# PCB_1b.net
KiCad netlist of a schematic drawn in EAGLE
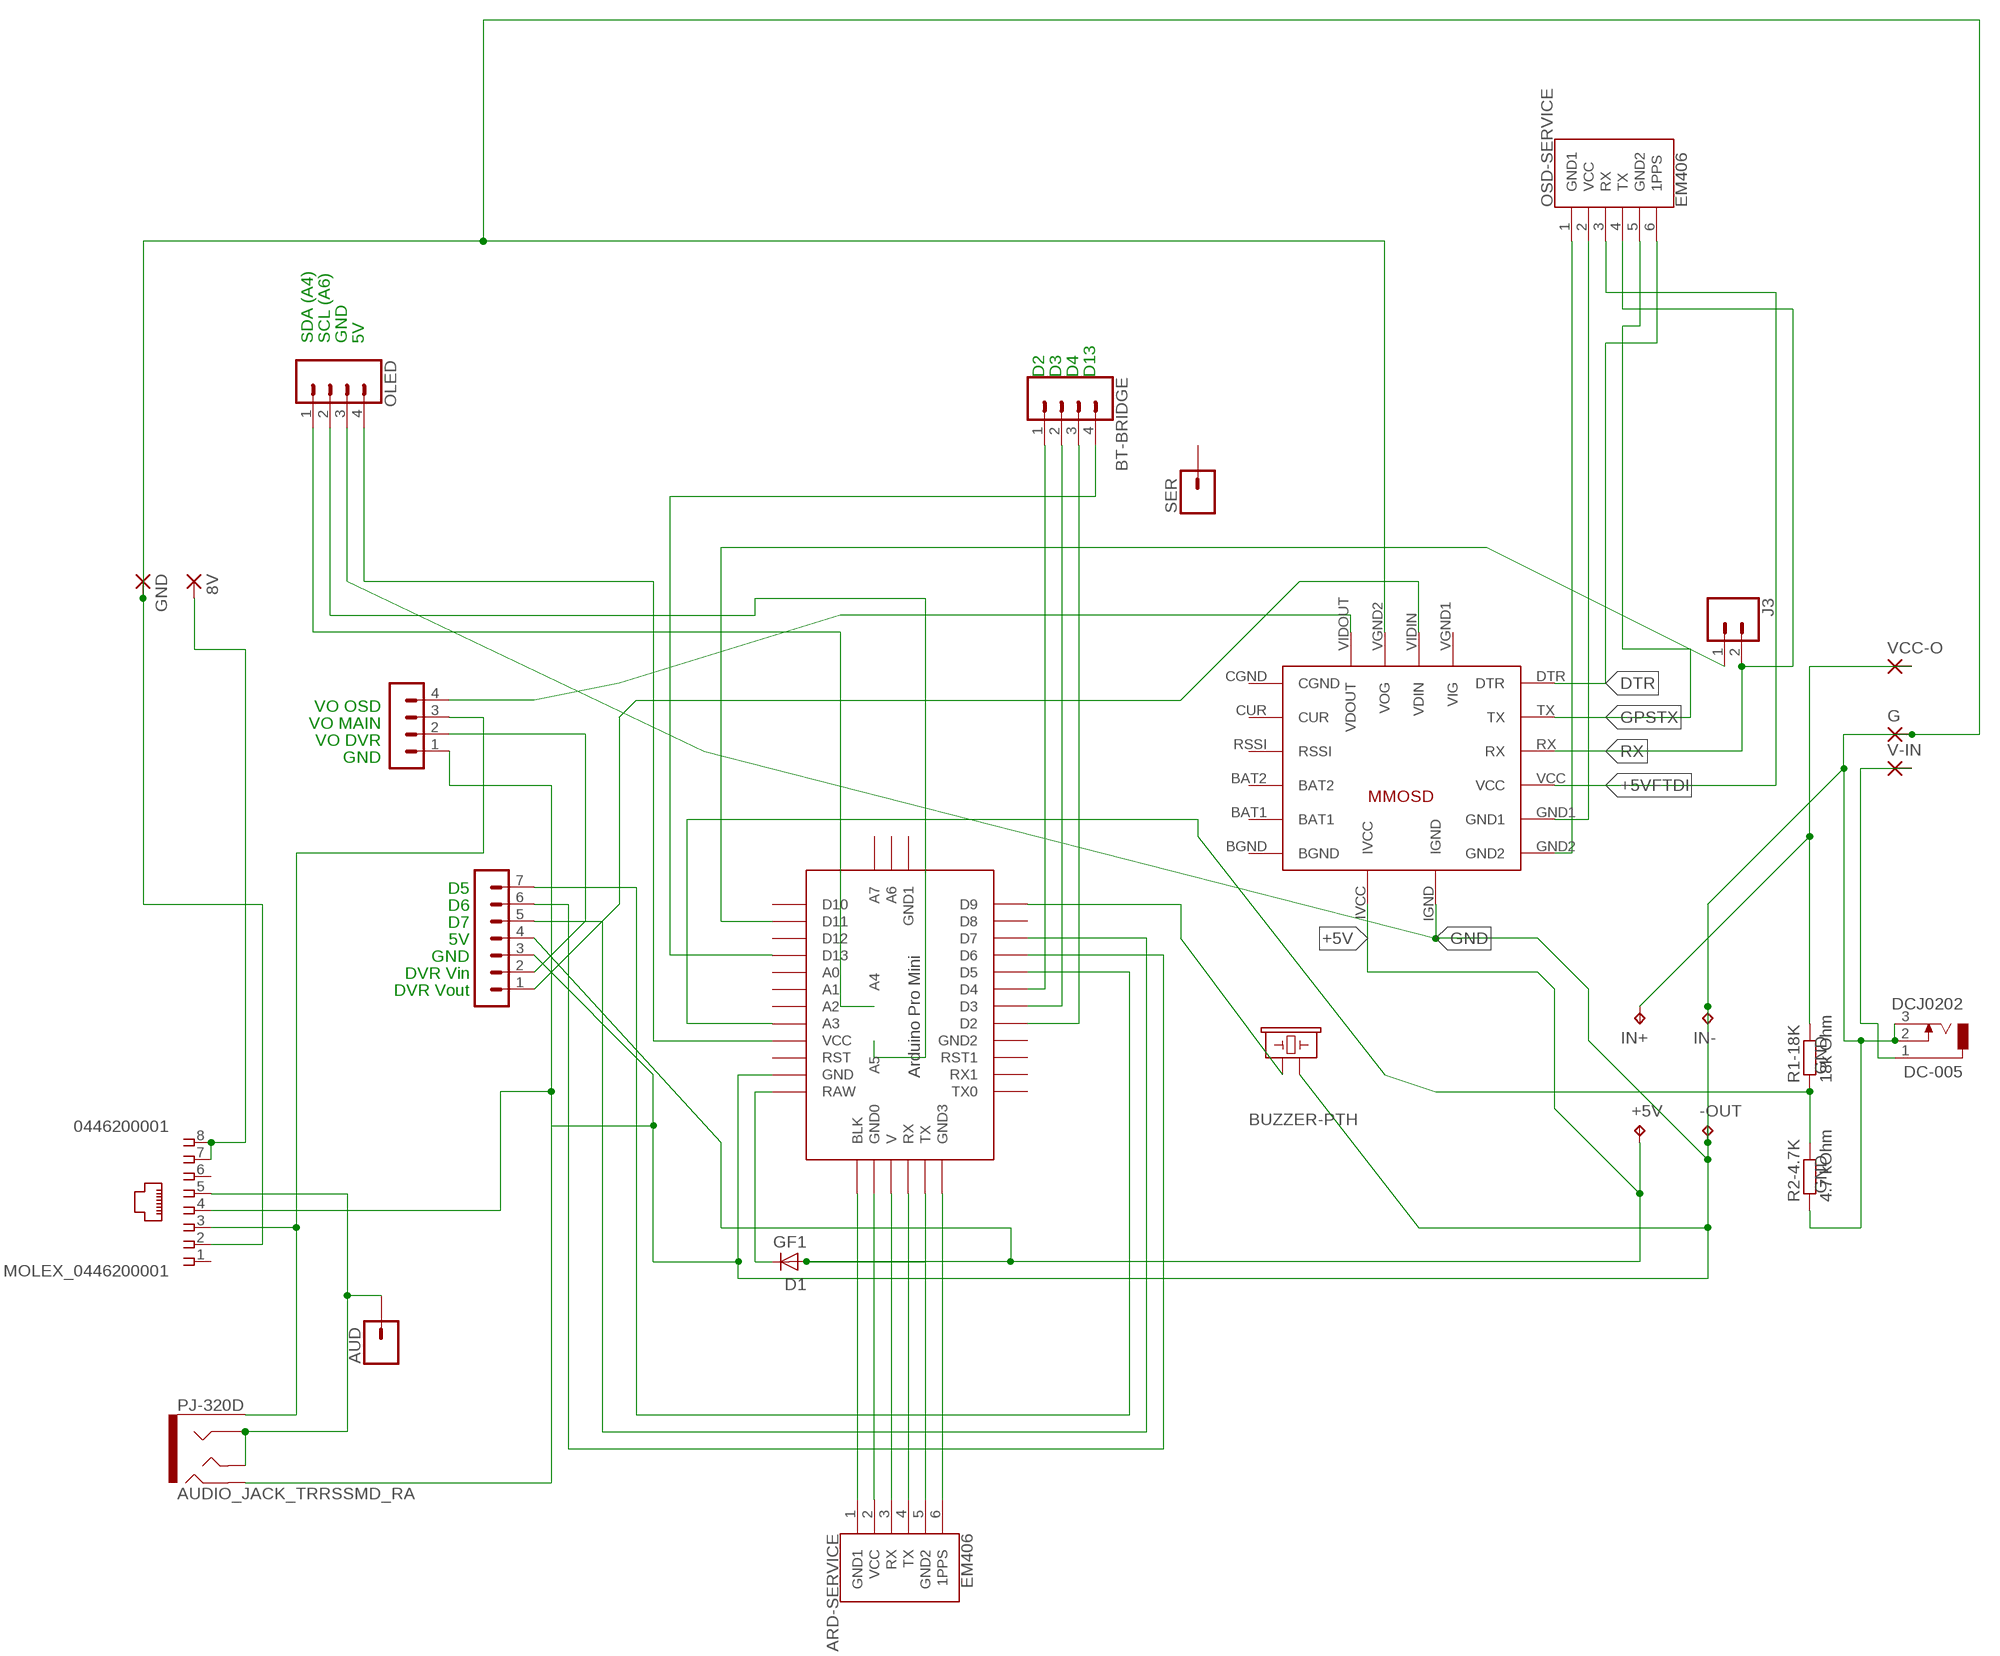
[diagram p0: schematic, sheet 1]

(export (version "E")
  (design (tool "Eeschema 10.0.6"))
  (components
    (comp (ref "+5V")
      (value "TPTP20SQ")
      (footprint "eagle-import:TP20SQ")
      (libsource (lib "eagle-import") (part "TPTP20SQ"))
    )
    (comp (ref "-OUT")
      (value "TPTP20SQ")
      (footprint "eagle-import:TP20SQ")
      (libsource (lib "eagle-import") (part "TPTP20SQ"))
    )
    (comp (ref "8V")
      (value "2,54/1,1")
      (footprint "eagle-import:2,54_1,1")
      (libsource (lib "eagle-import") (part "2,54/1,1"))
    )
    (comp (ref "ARD-SERVICE")
      (value "EM406")
      (footprint "eagle-import:1X06-1MM")
      (libsource (lib "eagle-import") (part "EM406"))
    )
    (comp (ref "AUD")
      (value "CONN_01")
      (footprint "eagle-import:1X01")
      (libsource (lib "eagle-import") (part "CONN_01"))
    )
    (comp (ref "BT-BRIDGE")
      (value "CONN_04")
      (footprint "eagle-import:1X04")
      (libsource (lib "eagle-import") (part "CONN_04"))
    )
    (comp (ref "BUZZ")
      (value "BUZZER-PTH")
      (footprint "eagle-import:BUZZER-12MM")
      (fields (field (name "SPICEPREFIX") "X"))
      (libsource (lib "eagle-import") (part "BUZZER-PTH"))
    )
    (comp (ref "D1")
      (value "GF1")
      (footprint "eagle-import:SMA-DO214AC")
      (libsource (lib "eagle-import") (part "GF1"))
    )
    (comp (ref "DC-005")
      (value "DCJ0202")
      (footprint "eagle-import:DCJ0202")
      (libsource (lib "eagle-import") (part "DCJ0202"))
    )
    (comp (ref "DVR/MODULE-IO")
      (value "MA07-1")
      (footprint "eagle-import:MA07-1")
      (libsource (lib "eagle-import") (part "MA07-1"))
    )
    (comp (ref "G")
      (value "2,54/1,1")
      (footprint "eagle-import:2,54_1,1")
      (libsource (lib "eagle-import") (part "2,54/1,1"))
    )
    (comp (ref "GND")
      (value "2,54/1,1")
      (footprint "eagle-import:2,54_1,1")
      (libsource (lib "eagle-import") (part "2,54/1,1"))
    )
    (comp (ref "IN+")
      (value "TPTP20SQ")
      (footprint "eagle-import:TP20SQ")
      (libsource (lib "eagle-import") (part "TPTP20SQ"))
    )
    (comp (ref "IN-")
      (value "TPTP20SQ")
      (footprint "eagle-import:TP20SQ")
      (libsource (lib "eagle-import") (part "TPTP20SQ"))
    )
    (comp (ref "J3")
      (value "CONN_02")
      (footprint "eagle-import:1X02")
      (libsource (lib "eagle-import") (part "CONN_02"))
    )
    (comp (ref "MINIMOSD")
      (value "MICROMINIMOSDPWR")
      (footprint "eagle-import:MMOSDNVDVID")
      (libsource (lib "eagle-import") (part "MICROMINIMOSDPWR"))
    )
    (comp (ref "MOLEX_0446200001")
      (value "0446200001")
      (footprint "eagle-import:0446200001")
      (fields (field (name "MF") "MOLEX"))
      (libsource (lib "eagle-import") (part "0446200001"))
    )
    (comp (ref "OLED")
      (value "CONN_04")
      (footprint "eagle-import:1X04")
      (libsource (lib "eagle-import") (part "CONN_04"))
    )
    (comp (ref "OSD-SERVICE")
      (value "EM406")
      (footprint "eagle-import:1X06-1MM")
      (libsource (lib "eagle-import") (part "EM406"))
    )
    (comp (ref "PJ-320D")
      (value "AUDIO_JACK_TRRSSMD_RA")
      (footprint "eagle-import:AUDIO_JACK_3.5MM_TRRS_SMD_RA")
      (libsource (lib "eagle-import") (part "AUDIO_JACK_TRRSSMD_RA"))
    )
    (comp (ref "R1-18K")
      (value "18k Ohm")
      (footprint "eagle-import:M1206")
      (libsource (lib "eagle-import") (part "R-EU_M1206"))
    )
    (comp (ref "R2-4.7K")
      (value "4.7 kOhm")
      (footprint "eagle-import:M1206")
      (libsource (lib "eagle-import") (part "R-EU_M1206"))
    )
    (comp (ref "SER")
      (value "CONN_01")
      (footprint "eagle-import:1X01")
      (libsource (lib "eagle-import") (part "CONN_01"))
    )
    (comp (ref "U$1")
      (value "ABK-PRO-MINI")
      (footprint "eagle-import:ABK-PRO-MINI")
      (libsource (lib "eagle-import") (part "ABK-PRO-MINI"))
    )
    (comp (ref "V-IN")
      (value "2,54/1,1")
      (footprint "eagle-import:2,54_1,1")
      (libsource (lib "eagle-import") (part "2,54/1,1"))
    )
    (comp (ref "V-IO")
      (value "MA04-1")
      (footprint "eagle-import:MA04-1")
      (libsource (lib "eagle-import") (part "MA04-1"))
    )
    (comp (ref "VCC-O")
      (value "2,54/1,1")
      (footprint "eagle-import:2,54_1,1")
      (libsource (lib "eagle-import") (part "2,54/1,1"))
    )
  )
  (nets
    (net (code "1") (name "+5V") (class "Default")
      (node (ref "+5V") (pin "TP") (pinfunction "TP_TP") (pintype "input"))
      (node (ref "D1") (pin "A") (pinfunction "A_A") (pintype "passive"))
      (node (ref "DVR/MODULE-IO") (pin "4") (pinfunction "4_4") (pintype "passive"))
      (node (ref "MINIMOSD") (pin "IVCC") (pinfunction "IVCC_IVCC") (pintype "power_in"))
    )
    (net (code "2") (name "+5VFTDI") (class "Default")
      (node (ref "MINIMOSD") (pin "VCC") (pinfunction "VCC_VCC") (pintype "power_in"))
      (node (ref "OSD-SERVICE") (pin "3") (pinfunction "RX_3") (pintype "bidirectional"))
    )
    (net (code "3") (name "/BAT1") (class "Default")
      (node (ref "MINIMOSD") (pin "BAT1") (pinfunction "BAT1_BAT1") (pintype "power_in"))
    )
    (net (code "4") (name "/BAT2") (class "Default")
      (node (ref "MINIMOSD") (pin "BAT2") (pinfunction "BAT2_BAT2") (pintype "power_in"))
    )
    (net (code "5") (name "/BGND") (class "Default")
      (node (ref "MINIMOSD") (pin "BGND") (pinfunction "BGND_BGND") (pintype "power_in"))
    )
    (net (code "6") (name "/CGND") (class "Default")
      (node (ref "MINIMOSD") (pin "CGND") (pinfunction "CGND_CGND") (pintype "power_in"))
    )
    (net (code "7") (name "DTR") (class "Default")
      (node (ref "MINIMOSD") (pin "DTR") (pinfunction "DTR_DTR") (pintype "bidirectional"))
      (node (ref "OSD-SERVICE") (pin "6") (pinfunction "1PPS_6") (pintype "bidirectional"))
    )
    (net (code "8") (name "GND") (class "Default")
      (node (ref "-OUT") (pin "TP") (pinfunction "TP_TP") (pintype "input"))
      (node (ref "BUZZ") (pin "-") (pinfunction "2_-") (pintype "passive"))
      (node (ref "DC-005") (pin "2") (pinfunction "2_2") (pintype "passive"))
      (node (ref "DC-005") (pin "3") (pinfunction "3_3") (pintype "passive"))
      (node (ref "DVR/MODULE-IO") (pin "3") (pinfunction "3_3") (pintype "passive"))
      (node (ref "G") (pin "1") (pinfunction "P_1") (pintype "passive"))
      (node (ref "GND") (pin "1") (pinfunction "P_1") (pintype "passive"))
      (node (ref "IN-") (pin "TP") (pinfunction "TP_TP") (pintype "input"))
      (node (ref "MINIMOSD") (pin "IGND") (pinfunction "IGND_IGND") (pintype "power_in"))
      (node (ref "MINIMOSD") (pin "VGND2") (pinfunction "VOG_VGND2") (pintype "output"))
      (node (ref "MOLEX_0446200001") (pin "2") (pinfunction "2_2") (pintype "passive"))
      (node (ref "MOLEX_0446200001") (pin "4") (pinfunction "4_4") (pintype "passive"))
      (node (ref "OLED") (pin "3") (pinfunction "3_3") (pintype "passive"))
      (node (ref "PJ-320D") (pin "RING2") (pinfunction "RING2_RING2") (pintype "bidirectional"))
      (node (ref "R2-4.7K") (pin "1") (pinfunction "1_1") (pintype "passive"))
      (node (ref "U$1") (pin "GND") (pinfunction "GND_GND") (pintype "bidirectional"))
      (node (ref "V-IO") (pin "1") (pinfunction "1_1") (pintype "passive"))
    )
    (net (code "9") (name "GPSTX") (class "Default")
      (node (ref "MINIMOSD") (pin "TX") (pinfunction "TX_TX") (pintype "output"))
      (node (ref "OSD-SERVICE") (pin "5") (pinfunction "GND2_5") (pintype "bidirectional"))
    )
    (net (code "10") (name "Net-(8V-P)") (class "Default")
      (node (ref "8V") (pin "1") (pinfunction "P_1") (pintype "passive"))
      (node (ref "MOLEX_0446200001") (pin "7") (pinfunction "7_7") (pintype "passive"))
      (node (ref "MOLEX_0446200001") (pin "8") (pinfunction "8_8") (pintype "passive"))
    )
    (net (code "11") (name "Net-(ARD-SERVICE-1PPS)") (class "Default")
      (node (ref "ARD-SERVICE") (pin "6") (pinfunction "1PPS_6") (pintype "bidirectional"))
      (node (ref "U$1") (pin "DTR") (pinfunction "GND3_DTR") (pintype "bidirectional"))
    )
    (net (code "12") (name "Net-(ARD-SERVICE-GND1)") (class "Default")
      (node (ref "ARD-SERVICE") (pin "1") (pinfunction "GND1_1") (pintype "bidirectional"))
      (node (ref "U$1") (pin "BLK") (pinfunction "BLK_BLK") (pintype "bidirectional"))
    )
    (net (code "13") (name "Net-(ARD-SERVICE-GND2)") (class "Default")
      (node (ref "ARD-SERVICE") (pin "5") (pinfunction "GND2_5") (pintype "bidirectional"))
      (node (ref "U$1") (pin "TX01") (pinfunction "TX_TX01") (pintype "bidirectional"))
    )
    (net (code "14") (name "Net-(ARD-SERVICE-RX)") (class "Default")
      (node (ref "ARD-SERVICE") (pin "3") (pinfunction "RX_3") (pintype "bidirectional"))
      (node (ref "U$1") (pin "5V") (pinfunction "V_5V") (pintype "bidirectional"))
    )
    (net (code "15") (name "Net-(ARD-SERVICE-TX)") (class "Default")
      (node (ref "ARD-SERVICE") (pin "4") (pinfunction "TX_4") (pintype "bidirectional"))
      (node (ref "U$1") (pin "RX01") (pinfunction "RX_RX01") (pintype "bidirectional"))
    )
    (net (code "16") (name "Net-(ARD-SERVICE-VCC)") (class "Default")
      (node (ref "ARD-SERVICE") (pin "2") (pinfunction "VCC_2") (pintype "bidirectional"))
      (node (ref "U$1") (pin "G") (pinfunction "GND0_G") (pintype "bidirectional"))
    )
    (net (code "17") (name "Net-(AUD-Pad1)") (class "Default")
      (node (ref "AUD") (pin "1") (pinfunction "1_1") (pintype "passive"))
      (node (ref "MOLEX_0446200001") (pin "5") (pinfunction "5_5") (pintype "passive"))
      (node (ref "PJ-320D") (pin "RING1") (pinfunction "RING1_RING1") (pintype "bidirectional"))
      (node (ref "PJ-320D") (pin "TIP") (pinfunction "TIP_TIP") (pintype "bidirectional"))
    )
    (net (code "18") (name "Net-(BT-BRIDGE-Pad1)") (class "Default")
      (node (ref "BT-BRIDGE") (pin "1") (pinfunction "1_1") (pintype "passive"))
      (node (ref "U$1") (pin "D4") (pinfunction "D4_D4") (pintype "bidirectional"))
    )
    (net (code "19") (name "Net-(BT-BRIDGE-Pad2)") (class "Default")
      (node (ref "BT-BRIDGE") (pin "2") (pinfunction "2_2") (pintype "passive"))
      (node (ref "U$1") (pin "D3") (pinfunction "D3_D3") (pintype "bidirectional"))
    )
    (net (code "20") (name "Net-(BT-BRIDGE-Pad3)") (class "Default")
      (node (ref "BT-BRIDGE") (pin "3") (pinfunction "3_3") (pintype "passive"))
      (node (ref "U$1") (pin "D2") (pinfunction "D2_D2") (pintype "bidirectional"))
    )
    (net (code "21") (name "Net-(BT-BRIDGE-Pad4)") (class "Default")
      (node (ref "BT-BRIDGE") (pin "4") (pinfunction "4_4") (pintype "passive"))
      (node (ref "U$1") (pin "D13") (pinfunction "D13_D13") (pintype "bidirectional"))
    )
    (net (code "22") (name "Net-(BUZZ-1)") (class "Default")
      (node (ref "BUZZ") (pin "+") (pinfunction "1_+") (pintype "passive"))
      (node (ref "U$1") (pin "D9") (pinfunction "D9_D9") (pintype "bidirectional"))
    )
    (net (code "23") (name "Net-(D1-C)") (class "Default")
      (node (ref "D1") (pin "K") (pinfunction "C_K") (pintype "passive"))
      (node (ref "U$1") (pin "RAW") (pinfunction "RAW_RAW") (pintype "bidirectional"))
    )
    (net (code "24") (name "Net-(DVR/MODULE-IO-Pad2)") (class "Default")
      (node (ref "DVR/MODULE-IO") (pin "2") (pinfunction "2_2") (pintype "passive"))
      (node (ref "V-IO") (pin "2") (pinfunction "2_2") (pintype "passive"))
    )
    (net (code "25") (name "Net-(DVR/MODULE-IO-Pad5)") (class "Default")
      (node (ref "DVR/MODULE-IO") (pin "5") (pinfunction "5_5") (pintype "passive"))
      (node (ref "U$1") (pin "D7") (pinfunction "D7_D7") (pintype "bidirectional"))
    )
    (net (code "26") (name "Net-(DVR/MODULE-IO-Pad6)") (class "Default")
      (node (ref "DVR/MODULE-IO") (pin "6") (pinfunction "6_6") (pintype "passive"))
      (node (ref "U$1") (pin "D6") (pinfunction "D6_D6") (pintype "bidirectional"))
    )
    (net (code "27") (name "Net-(DVR/MODULE-IO-Pad7)") (class "Default")
      (node (ref "DVR/MODULE-IO") (pin "7") (pinfunction "7_7") (pintype "passive"))
      (node (ref "U$1") (pin "D5") (pinfunction "D5_D5") (pintype "bidirectional"))
    )
    (net (code "28") (name "Net-(J3-Pad1)") (class "Default")
      (node (ref "J3") (pin "1") (pinfunction "1_1") (pintype "passive"))
      (node (ref "U$1") (pin "D11") (pinfunction "D11_D11") (pintype "bidirectional"))
    )
    (net (code "29") (name "Net-(MINIMOSD-VDIN)") (class "Default")
      (node (ref "DVR/MODULE-IO") (pin "1") (pinfunction "1_1") (pintype "passive"))
      (node (ref "MINIMOSD") (pin "VIDIN") (pinfunction "VDIN_VIDIN") (pintype "input"))
    )
    (net (code "30") (name "Net-(MINIMOSD-VDOUT)") (class "Default")
      (node (ref "MINIMOSD") (pin "VIDOUT") (pinfunction "VDOUT_VIDOUT") (pintype "output"))
      (node (ref "V-IO") (pin "4") (pinfunction "4_4") (pintype "passive"))
    )
    (net (code "31") (name "Net-(MOLEX_0446200001-Pad3)") (class "Default")
      (node (ref "MOLEX_0446200001") (pin "3") (pinfunction "3_3") (pintype "passive"))
      (node (ref "PJ-320D") (pin "EARTH") (pinfunction "EARTH_EARTH") (pintype "bidirectional"))
      (node (ref "V-IO") (pin "3") (pinfunction "3_3") (pintype "passive"))
    )
    (net (code "32") (name "Net-(OLED-Pad1)") (class "Default")
      (node (ref "OLED") (pin "1") (pinfunction "1_1") (pintype "passive"))
      (node (ref "U$1") (pin "A4") (pinfunction "A4_A4") (pintype "bidirectional"))
    )
    (net (code "33") (name "Net-(OLED-Pad2)") (class "Default")
      (node (ref "OLED") (pin "2") (pinfunction "2_2") (pintype "passive"))
      (node (ref "U$1") (pin "A5") (pinfunction "A5_A5") (pintype "bidirectional"))
    )
    (net (code "34") (name "Net-(OLED-Pad4)") (class "Default")
      (node (ref "OLED") (pin "4") (pinfunction "4_4") (pintype "passive"))
      (node (ref "U$1") (pin "VCC") (pinfunction "VCC_VCC") (pintype "bidirectional"))
    )
    (net (code "35") (name "Net-(OSD-SERVICE-GND1)") (class "Default")
      (node (ref "MINIMOSD") (pin "GND2") (pinfunction "GND2_GND2") (pintype "power_in"))
      (node (ref "OSD-SERVICE") (pin "1") (pinfunction "GND1_1") (pintype "bidirectional"))
    )
    (net (code "36") (name "Net-(OSD-SERVICE-VCC)") (class "Default")
      (node (ref "MINIMOSD") (pin "GND1") (pinfunction "GND1_GND1") (pintype "power_in"))
      (node (ref "OSD-SERVICE") (pin "2") (pinfunction "VCC_2") (pintype "bidirectional"))
    )
    (net (code "37") (name "Net-(U$1-A3)") (class "Default")
      (node (ref "R1-18K") (pin "1") (pinfunction "1_1") (pintype "passive"))
      (node (ref "R2-4.7K") (pin "2") (pinfunction "2_2") (pintype "passive"))
      (node (ref "U$1") (pin "A0") (pinfunction "A3_A0") (pintype "bidirectional"))
    )
    (net (code "38") (name "Net-(V-IN-P)") (class "Default")
      (node (ref "DC-005") (pin "1") (pinfunction "1_1") (pintype "passive"))
      (node (ref "V-IN") (pin "1") (pinfunction "P_1") (pintype "passive"))
    )
    (net (code "39") (name "Net-(VCC-O-P)") (class "Default")
      (node (ref "IN+") (pin "TP") (pinfunction "TP_TP") (pintype "input"))
      (node (ref "R1-18K") (pin "2") (pinfunction "2_2") (pintype "passive"))
      (node (ref "VCC-O") (pin "1") (pinfunction "P_1") (pintype "passive"))
    )
    (net (code "40") (name "RX") (class "Default")
      (node (ref "J3") (pin "2") (pinfunction "2_2") (pintype "passive"))
      (node (ref "MINIMOSD") (pin "RX") (pinfunction "RX_RX") (pintype "input"))
      (node (ref "OSD-SERVICE") (pin "4") (pinfunction "TX_4") (pintype "bidirectional"))
    )
    (net (code "41") (name "unconnected-(MINIMOSD-PadCUR)") (class "Default")
      (node (ref "MINIMOSD") (pin "CUR") (pinfunction "CUR_CUR") (pintype "bidirectional"))
    )
    (net (code "42") (name "unconnected-(MINIMOSD-PadRSSI)") (class "Default")
      (node (ref "MINIMOSD") (pin "RSSI") (pinfunction "RSSI_RSSI") (pintype "bidirectional"))
    )
    (net (code "43") (name "unconnected-(MINIMOSD-VIG-PadVGND1)") (class "Default")
      (node (ref "MINIMOSD") (pin "VGND1") (pinfunction "VIG_VGND1") (pintype "input"))
    )
    (net (code "44") (name "unconnected-(MOLEX_0446200001-Pad1)") (class "Default")
      (node (ref "MOLEX_0446200001") (pin "1") (pinfunction "1_1") (pintype "passive"))
    )
    (net (code "45") (name "unconnected-(MOLEX_0446200001-Pad6)") (class "Default")
      (node (ref "MOLEX_0446200001") (pin "6") (pinfunction "6_6") (pintype "passive"))
    )
    (net (code "46") (name "unconnected-(SER-Pad1)") (class "Default")
      (node (ref "SER") (pin "1") (pinfunction "1_1") (pintype "passive"))
    )
    (net (code "47") (name "unconnected-(U$1-A0-PadA3)") (class "Default")
      (node (ref "U$1") (pin "A3") (pinfunction "A0_A3") (pintype "bidirectional"))
    )
    (net (code "48") (name "unconnected-(U$1-A1-PadA2)") (class "Default")
      (node (ref "U$1") (pin "A2") (pinfunction "A1_A2") (pintype "bidirectional"))
    )
    (net (code "49") (name "unconnected-(U$1-A2-PadA1)") (class "Default")
      (node (ref "U$1") (pin "A1") (pinfunction "A2_A1") (pintype "bidirectional"))
    )
    (net (code "50") (name "unconnected-(U$1-GND1-PadGND4)") (class "Default")
      (node (ref "U$1") (pin "GND4") (pinfunction "GND1_GND4") (pintype "bidirectional"))
    )
    (net (code "51") (name "unconnected-(U$1-GND2-PadGND1)") (class "Default")
      (node (ref "U$1") (pin "GND1") (pinfunction "GND2_GND1") (pintype "bidirectional"))
    )
    (net (code "52") (name "unconnected-(U$1-PadA6)") (class "Default")
      (node (ref "U$1") (pin "A6") (pinfunction "A6_A6") (pintype "bidirectional"))
    )
    (net (code "53") (name "unconnected-(U$1-PadA7)") (class "Default")
      (node (ref "U$1") (pin "A7") (pinfunction "A7_A7") (pintype "bidirectional"))
    )
    (net (code "54") (name "unconnected-(U$1-PadD8)") (class "Default")
      (node (ref "U$1") (pin "D8") (pinfunction "D8_D8") (pintype "bidirectional"))
    )
    (net (code "55") (name "unconnected-(U$1-PadD10)") (class "Default")
      (node (ref "U$1") (pin "D10") (pinfunction "D10_D10") (pintype "bidirectional"))
    )
    (net (code "56") (name "unconnected-(U$1-PadD12)") (class "Default")
      (node (ref "U$1") (pin "D12") (pinfunction "D12_D12") (pintype "bidirectional"))
    )
    (net (code "57") (name "unconnected-(U$1-PadRST)") (class "Default")
      (node (ref "U$1") (pin "RST") (pinfunction "RST_RST") (pintype "bidirectional"))
    )
    (net (code "58") (name "unconnected-(U$1-PadRST1)") (class "Default")
      (node (ref "U$1") (pin "RST1") (pinfunction "RST1_RST1") (pintype "bidirectional"))
    )
    (net (code "59") (name "unconnected-(U$1-PadRX1)") (class "Default")
      (node (ref "U$1") (pin "RX1") (pinfunction "RX1_RX1") (pintype "bidirectional"))
    )
    (net (code "60") (name "unconnected-(U$1-PadTX0)") (class "Default")
      (node (ref "U$1") (pin "TX0") (pinfunction "TX0_TX0") (pintype "bidirectional"))
    )
  )
)
